# ECGLeads.net
KiCad netlist of a schematic drawn in Altium Designer
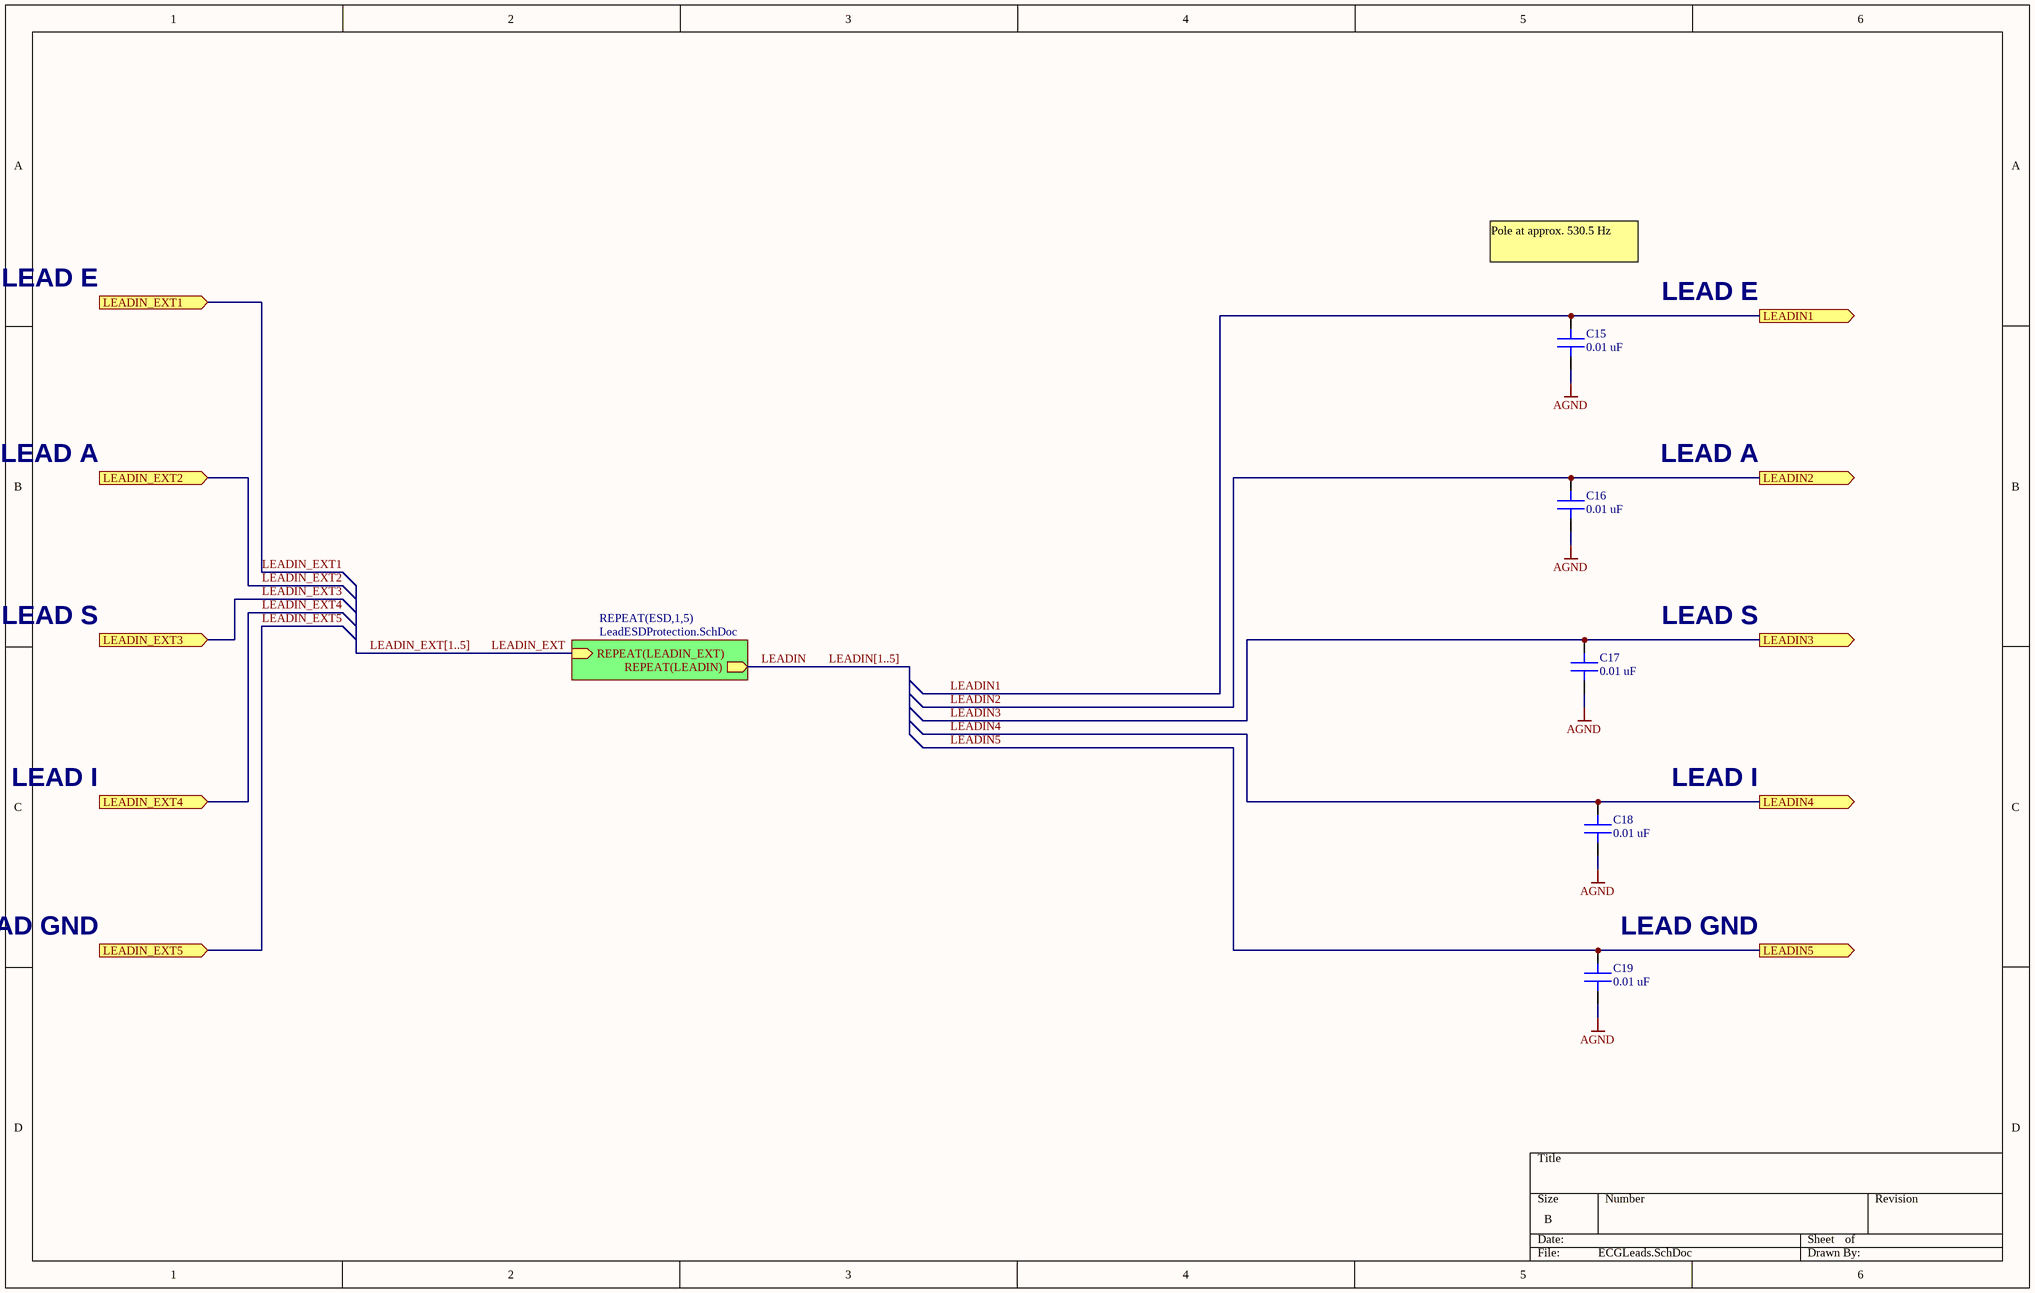
[diagram p0: ECGLeads.SchDoc]

(export (version "E")
  (design (tool "Eeschema 10.0.6"))
  (components
    (comp (ref "C15")
      (value "0.01 uF")
      (footprint "CAP_0603")
      (description "CAP CER 10000PF 50V 10% X7R 0603")
      (fields
        (field (name "MANUFACTURER") "TDK Corporation")
        (field (name "MANUFACTURER PART NUMBER") "C1608X7R1H103K080AA")
      )
      (libsource (lib "ECGLib") (part "CAP_GEN"))
    )
    (comp (ref "C16")
      (value "0.01 uF")
      (footprint "CAP_0603")
      (description "CAP CER 10000PF 50V 10% X7R 0603")
      (fields (field (name "Comment") "CAP CER 1200PF 50V 10% X7R 0603"))
      (libsource (lib "ECGLib") (part "CAP_GEN"))
    )
    (comp (ref "C17")
      (value "0.01 uF")
      (footprint "CAP_0603")
      (description "CAP CER 10000PF 50V 10% X7R 0603")
      (fields
        (field (name "MANUFACTURER") "TDK Corporation")
        (field (name "MANUFACTURER PART NUMBER") "C1608X7R1H103K080AA")
      )
      (libsource (lib "ECGLib") (part "CAP_GEN"))
    )
    (comp (ref "C18")
      (value "0.01 uF")
      (footprint "CAP_0603")
      (description "CAP CER 10000PF 50V 10% X7R 0603")
      (fields
        (field (name "MANUFACTURER") "TDK Corporation")
        (field (name "MANUFACTURER PART NUMBER") "C1608X7R1H103K080AA")
      )
      (libsource (lib "ECGLib") (part "CAP_GEN"))
    )
    (comp (ref "C19")
      (value "0.01 uF")
      (footprint "CAP_0603")
      (description "CAP CER 10000PF 50V 10% X7R 0603")
      (fields
        (field (name "MANUFACTURER") "TDK Corporation")
        (field (name "MANUFACTURER PART NUMBER") "C1608X7R1H103K080AA")
      )
      (libsource (lib "ECGLib") (part "CAP_GEN"))
    )
  )
  (nets
    (net (code "2") (name "/LEADIN1") (class "Default")
      (node (ref "C15") (pin "2") (pinfunction "2_2") (pintype "passive"))
    )
    (net (code "3") (name "/LEADIN2") (class "Default")
      (node (ref "C16") (pin "2") (pinfunction "2_2") (pintype "passive"))
    )
    (net (code "4") (name "/LEADIN3") (class "Default")
      (node (ref "C17") (pin "2") (pinfunction "2_2") (pintype "passive"))
    )
    (net (code "5") (name "/LEADIN4") (class "Default")
      (node (ref "C18") (pin "2") (pinfunction "2_2") (pintype "passive"))
    )
    (net (code "6") (name "/LEADIN5") (class "Default")
      (node (ref "C19") (pin "2") (pinfunction "2_2") (pintype "passive"))
    )
    (net (code "15") (name "AGND") (class "Default")
      (node (ref "C15") (pin "1") (pinfunction "1_1") (pintype "passive"))
      (node (ref "C16") (pin "1") (pinfunction "1_1") (pintype "passive"))
      (node (ref "C17") (pin "1") (pinfunction "1_1") (pintype "passive"))
      (node (ref "C18") (pin "1") (pinfunction "1_1") (pintype "passive"))
      (node (ref "C19") (pin "1") (pinfunction "1_1") (pintype "passive"))
    )
  )
)
